# TopLevel.net
KiCad netlist of a schematic drawn in Altium Designer
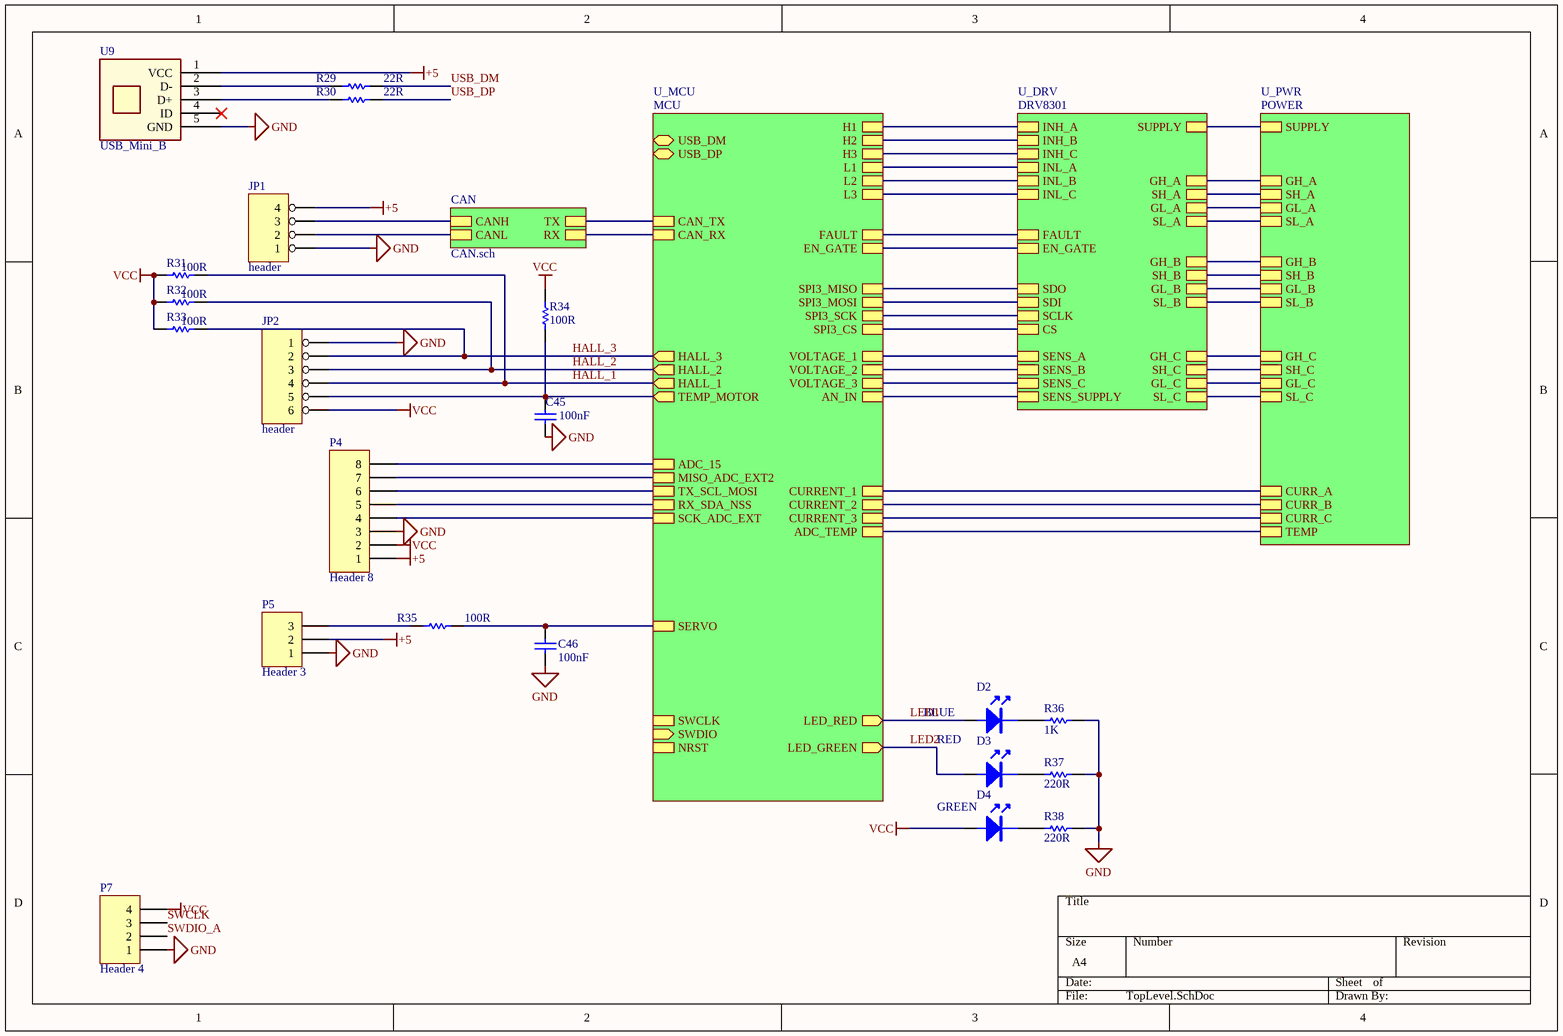
[diagram p0: TopLevel.SchDoc]

(export (version "E")
  (design (tool "Eeschema 10.0.6"))
  (components
    (comp (ref "C45")
      (value "100nF")
      (footprint "0603-1")
      (description "Capacitor")
      (fields (field (name "PUBLISHER") "Altium Limited"))
      (libsource (lib "My Footprint") (part "CAP"))
    )
    (comp (ref "C46")
      (value "100nF")
      (footprint "0603-1")
      (description "Capacitor")
      (fields (field (name "PUBLISHER") "Altium Limited"))
      (libsource (lib "My Footprint") (part "CAP"))
    )
    (comp (ref "D2")
      (value "BLUE")
      (footprint "0603-1")
      (description "LED 发光二极管")
      (libsource (lib "My Footprint") (part "LED"))
    )
    (comp (ref "D3")
      (value "RED")
      (footprint "0603-1")
      (description "LED 发光二极管")
      (libsource (lib "My Footprint") (part "LED"))
    )
    (comp (ref "D4")
      (value "GREEN")
      (footprint "0603-1")
      (description "LED 发光二极管")
      (libsource (lib "My Footprint") (part "LED"))
    )
    (comp (ref "JP1")
      (value "header")
      (footprint "HDR1X4")
      (libsource (lib "My Footprint") (part "HEADER 4"))
    )
    (comp (ref "JP2") (value "header") (footprint "SMD-6") (libsource (lib "My Footprint") (part "HEADER 6")))
    (comp (ref "P4")
      (value "Header 8")
      (footprint "HDR1X8")
      (description "Header, 8-Pin")
      (fields (field (name "PUBLISHER") "Altium Limited"))
      (libsource (lib "Miscellaneous Connectors") (part "Header 8"))
    )
    (comp (ref "P5")
      (value "Header 3")
      (footprint "HDR1X3")
      (description "Header, 3-Pin")
      (fields (field (name "PUBLISHER") "Altium Limited"))
      (libsource (lib "Miscellaneous Connectors") (part "Header 3"))
    )
    (comp (ref "P7")
      (value "Header 4")
      (footprint "HDR1X4")
      (description "Header, 4-Pin")
      (fields (field (name "PUBLISHER") "Altium Limited"))
      (libsource (lib "Miscellaneous Connectors") (part "Header 4"))
    )
    (comp (ref "R29")
      (value "22R")
      (footprint "0603-1")
      (description "Resistor")
      (fields (field (name "PUBLISHER") "Altium Limited"))
      (libsource (lib "My Footprint") (part "RES"))
    )
    (comp (ref "R30")
      (value "22R")
      (footprint "0603-1")
      (description "Resistor")
      (fields (field (name "PUBLISHER") "Altium Limited"))
      (libsource (lib "My Footprint") (part "RES"))
    )
    (comp (ref "R31")
      (value "100R")
      (footprint "0603-1")
      (description "Resistor")
      (fields (field (name "PUBLISHER") "Altium Limited"))
      (libsource (lib "My Footprint") (part "RES"))
    )
    (comp (ref "R32")
      (value "100R")
      (footprint "0603-1")
      (description "Resistor")
      (fields (field (name "PUBLISHER") "Altium Limited"))
      (libsource (lib "My Footprint") (part "RES"))
    )
    (comp (ref "R33")
      (value "100R")
      (footprint "0603-1")
      (description "Resistor")
      (fields (field (name "PUBLISHER") "Altium Limited"))
      (libsource (lib "My Footprint") (part "RES"))
    )
    (comp (ref "R34")
      (value "100R")
      (footprint "0603-1")
      (description "Resistor")
      (fields (field (name "PUBLISHER") "Altium Limited"))
      (libsource (lib "My Footprint") (part "RES"))
    )
    (comp (ref "R35")
      (value "100R")
      (footprint "0603-1")
      (description "Resistor")
      (fields (field (name "PUBLISHER") "Altium Limited"))
      (libsource (lib "My Footprint") (part "RES"))
    )
    (comp (ref "R36")
      (value "1K")
      (footprint "0603-1")
      (description "Resistor")
      (fields (field (name "PUBLISHER") "Altium Limited"))
      (libsource (lib "My Footprint") (part "RES"))
    )
    (comp (ref "R37")
      (value "220R")
      (footprint "0603-1")
      (description "Resistor")
      (fields (field (name "PUBLISHER") "Altium Limited"))
      (libsource (lib "My Footprint") (part "RES"))
    )
    (comp (ref "R38")
      (value "220R")
      (footprint "0603-1")
      (description "Resistor")
      (fields (field (name "PUBLISHER") "Altium Limited"))
      (libsource (lib "My Footprint") (part "RES"))
    )
    (comp (ref "U9")
      (value "USB_Mini_B")
      (footprint "Micro_USB")
      (libsource (lib "My Footprint") (part "USB_Mini_B"))
    )
  )
  (nets
    (net (code "1") (name "+5") (class "Default")
      (node (ref "JP1") (pin "4") (pinfunction "4_4") (pintype "passive"))
      (node (ref "P4") (pin "1") (pinfunction "1_1") (pintype "passive"))
      (node (ref "P5") (pin "2") (pinfunction "2_2") (pintype "passive"))
      (node (ref "U9") (pin "1") (pinfunction "VCC_1") (pintype "passive"))
    )
    (net (code "2") (name "/ADC_15") (class "Default")
      (node (ref "P4") (pin "8") (pinfunction "8_8") (pintype "passive"))
    )
    (net (code "5") (name "/CANH") (class "Default")
      (node (ref "JP1") (pin "3") (pinfunction "3_3") (pintype "passive"))
    )
    (net (code "6") (name "/CANL") (class "Default")
      (node (ref "JP1") (pin "2") (pinfunction "2_2") (pintype "passive"))
    )
    (net (code "24") (name "/HALL_1") (class "Default")
      (node (ref "JP2") (pin "4") (pinfunction "4_4") (pintype "passive"))
      (node (ref "R31") (pin "1") (pinfunction "1_1") (pintype "passive"))
    )
    (net (code "25") (name "/HALL_2") (class "Default")
      (node (ref "JP2") (pin "3") (pinfunction "3_3") (pintype "passive"))
      (node (ref "R32") (pin "1") (pinfunction "1_1") (pintype "passive"))
    )
    (net (code "26") (name "/HALL_3") (class "Default")
      (node (ref "JP2") (pin "2") (pinfunction "2_2") (pintype "passive"))
      (node (ref "R33") (pin "1") (pinfunction "1_1") (pintype "passive"))
    )
    (net (code "30") (name "/LED1") (class "Default")
      (node (ref "D2") (pin "1") (pinfunction "A_1") (pintype "passive"))
    )
    (net (code "31") (name "/LED2") (class "Default")
      (node (ref "D3") (pin "1") (pinfunction "A_1") (pintype "passive"))
    )
    (net (code "32") (name "/MISO_ADC_EXT2") (class "Default")
      (node (ref "P4") (pin "7") (pinfunction "7_7") (pintype "passive"))
    )
    (net (code "34") (name "/RX_SDA_NSS") (class "Default")
      (node (ref "P4") (pin "5") (pinfunction "5_5") (pintype "passive"))
    )
    (net (code "35") (name "/SCK_ADC_EXT") (class "Default")
      (node (ref "P4") (pin "4") (pinfunction "4_4") (pintype "passive"))
    )
    (net (code "42") (name "/SERVO") (class "Default")
      (node (ref "C46") (pin "1") (pinfunction "1_1") (pintype "passive"))
      (node (ref "R35") (pin "2") (pinfunction "2_2") (pintype "passive"))
    )
    (net (code "50") (name "/SWCLK") (class "Default")
      (node (ref "P7") (pin "3") (pinfunction "3_3") (pintype "passive"))
    )
    (net (code "53") (name "/SWDIO_A") (class "Default")
      (node (ref "P7") (pin "2") (pinfunction "2_2") (pintype "passive"))
    )
    (net (code "54") (name "/TEMP_MOTOR") (class "Default")
      (node (ref "C45") (pin "1") (pinfunction "1_1") (pintype "passive"))
      (node (ref "JP2") (pin "5") (pinfunction "5_5") (pintype "passive"))
      (node (ref "R34") (pin "2") (pinfunction "2_2") (pintype "passive"))
    )
    (net (code "55") (name "/TX_SCL_MOSI") (class "Default")
      (node (ref "P4") (pin "6") (pinfunction "6_6") (pintype "passive"))
    )
    (net (code "56") (name "/USB_DM") (class "Default")
      (node (ref "R29") (pin "2") (pinfunction "2_2") (pintype "passive"))
    )
    (net (code "58") (name "/USB_DP") (class "Default")
      (node (ref "R30") (pin "2") (pinfunction "2_2") (pintype "passive"))
    )
    (net (code "60") (name "GND") (class "Default")
      (node (ref "C45") (pin "2") (pinfunction "2_2") (pintype "passive"))
      (node (ref "C46") (pin "2") (pinfunction "2_2") (pintype "passive"))
      (node (ref "JP1") (pin "1") (pinfunction "1_1") (pintype "passive"))
      (node (ref "JP2") (pin "1") (pinfunction "1_1") (pintype "passive"))
      (node (ref "P4") (pin "3") (pinfunction "3_3") (pintype "passive"))
      (node (ref "P5") (pin "1") (pinfunction "1_1") (pintype "passive"))
      (node (ref "P7") (pin "1") (pinfunction "1_1") (pintype "passive"))
      (node (ref "R36") (pin "2") (pinfunction "2_2") (pintype "passive"))
      (node (ref "R37") (pin "2") (pinfunction "2_2") (pintype "passive"))
      (node (ref "R38") (pin "2") (pinfunction "2_2") (pintype "passive"))
      (node (ref "U9") (pin "5") (pinfunction "GND_5") (pintype "passive"))
    )
    (net (code "61") (name "Net-(D2-K)") (class "Default")
      (node (ref "D2") (pin "2") (pinfunction "K_2") (pintype "passive"))
      (node (ref "R36") (pin "1") (pinfunction "1_1") (pintype "passive"))
    )
    (net (code "62") (name "Net-(D3-K)") (class "Default")
      (node (ref "D3") (pin "2") (pinfunction "K_2") (pintype "passive"))
      (node (ref "R37") (pin "1") (pinfunction "1_1") (pintype "passive"))
    )
    (net (code "63") (name "Net-(D4-K)") (class "Default")
      (node (ref "D4") (pin "2") (pinfunction "K_2") (pintype "passive"))
      (node (ref "R38") (pin "1") (pinfunction "1_1") (pintype "passive"))
    )
    (net (code "64") (name "Net-(P5-Pad3)") (class "Default")
      (node (ref "P5") (pin "3") (pinfunction "3_3") (pintype "passive"))
      (node (ref "R35") (pin "1") (pinfunction "1_1") (pintype "passive"))
    )
    (net (code "65") (name "Net-(U9-D+)") (class "Default")
      (node (ref "R30") (pin "1") (pinfunction "1_1") (pintype "passive"))
      (node (ref "U9") (pin "3") (pinfunction "D+_3") (pintype "passive"))
    )
    (net (code "66") (name "Net-(U9-D-)") (class "Default")
      (node (ref "R29") (pin "1") (pinfunction "1_1") (pintype "passive"))
      (node (ref "U9") (pin "2") (pinfunction "D-_2") (pintype "passive"))
    )
    (net (code "67") (name "VCC") (class "Default")
      (node (ref "D4") (pin "1") (pinfunction "A_1") (pintype "passive"))
      (node (ref "JP2") (pin "6") (pinfunction "6_6") (pintype "passive"))
      (node (ref "P4") (pin "2") (pinfunction "2_2") (pintype "passive"))
      (node (ref "P7") (pin "4") (pinfunction "4_4") (pintype "passive"))
      (node (ref "R31") (pin "2") (pinfunction "2_2") (pintype "passive"))
      (node (ref "R32") (pin "2") (pinfunction "2_2") (pintype "passive"))
      (node (ref "R33") (pin "2") (pinfunction "2_2") (pintype "passive"))
      (node (ref "R34") (pin "1") (pinfunction "1_1") (pintype "passive"))
    )
    (net (code "68") (name "unconnected-(U9-ID-Pad4)") (class "Default")
      (node (ref "U9") (pin "4") (pinfunction "ID_4") (pintype "passive+no_connect"))
    )
  )
)
